# Solar_Batter_Charger_SCH_2.net
KiCad netlist of a schematic drawn in Altium Designer
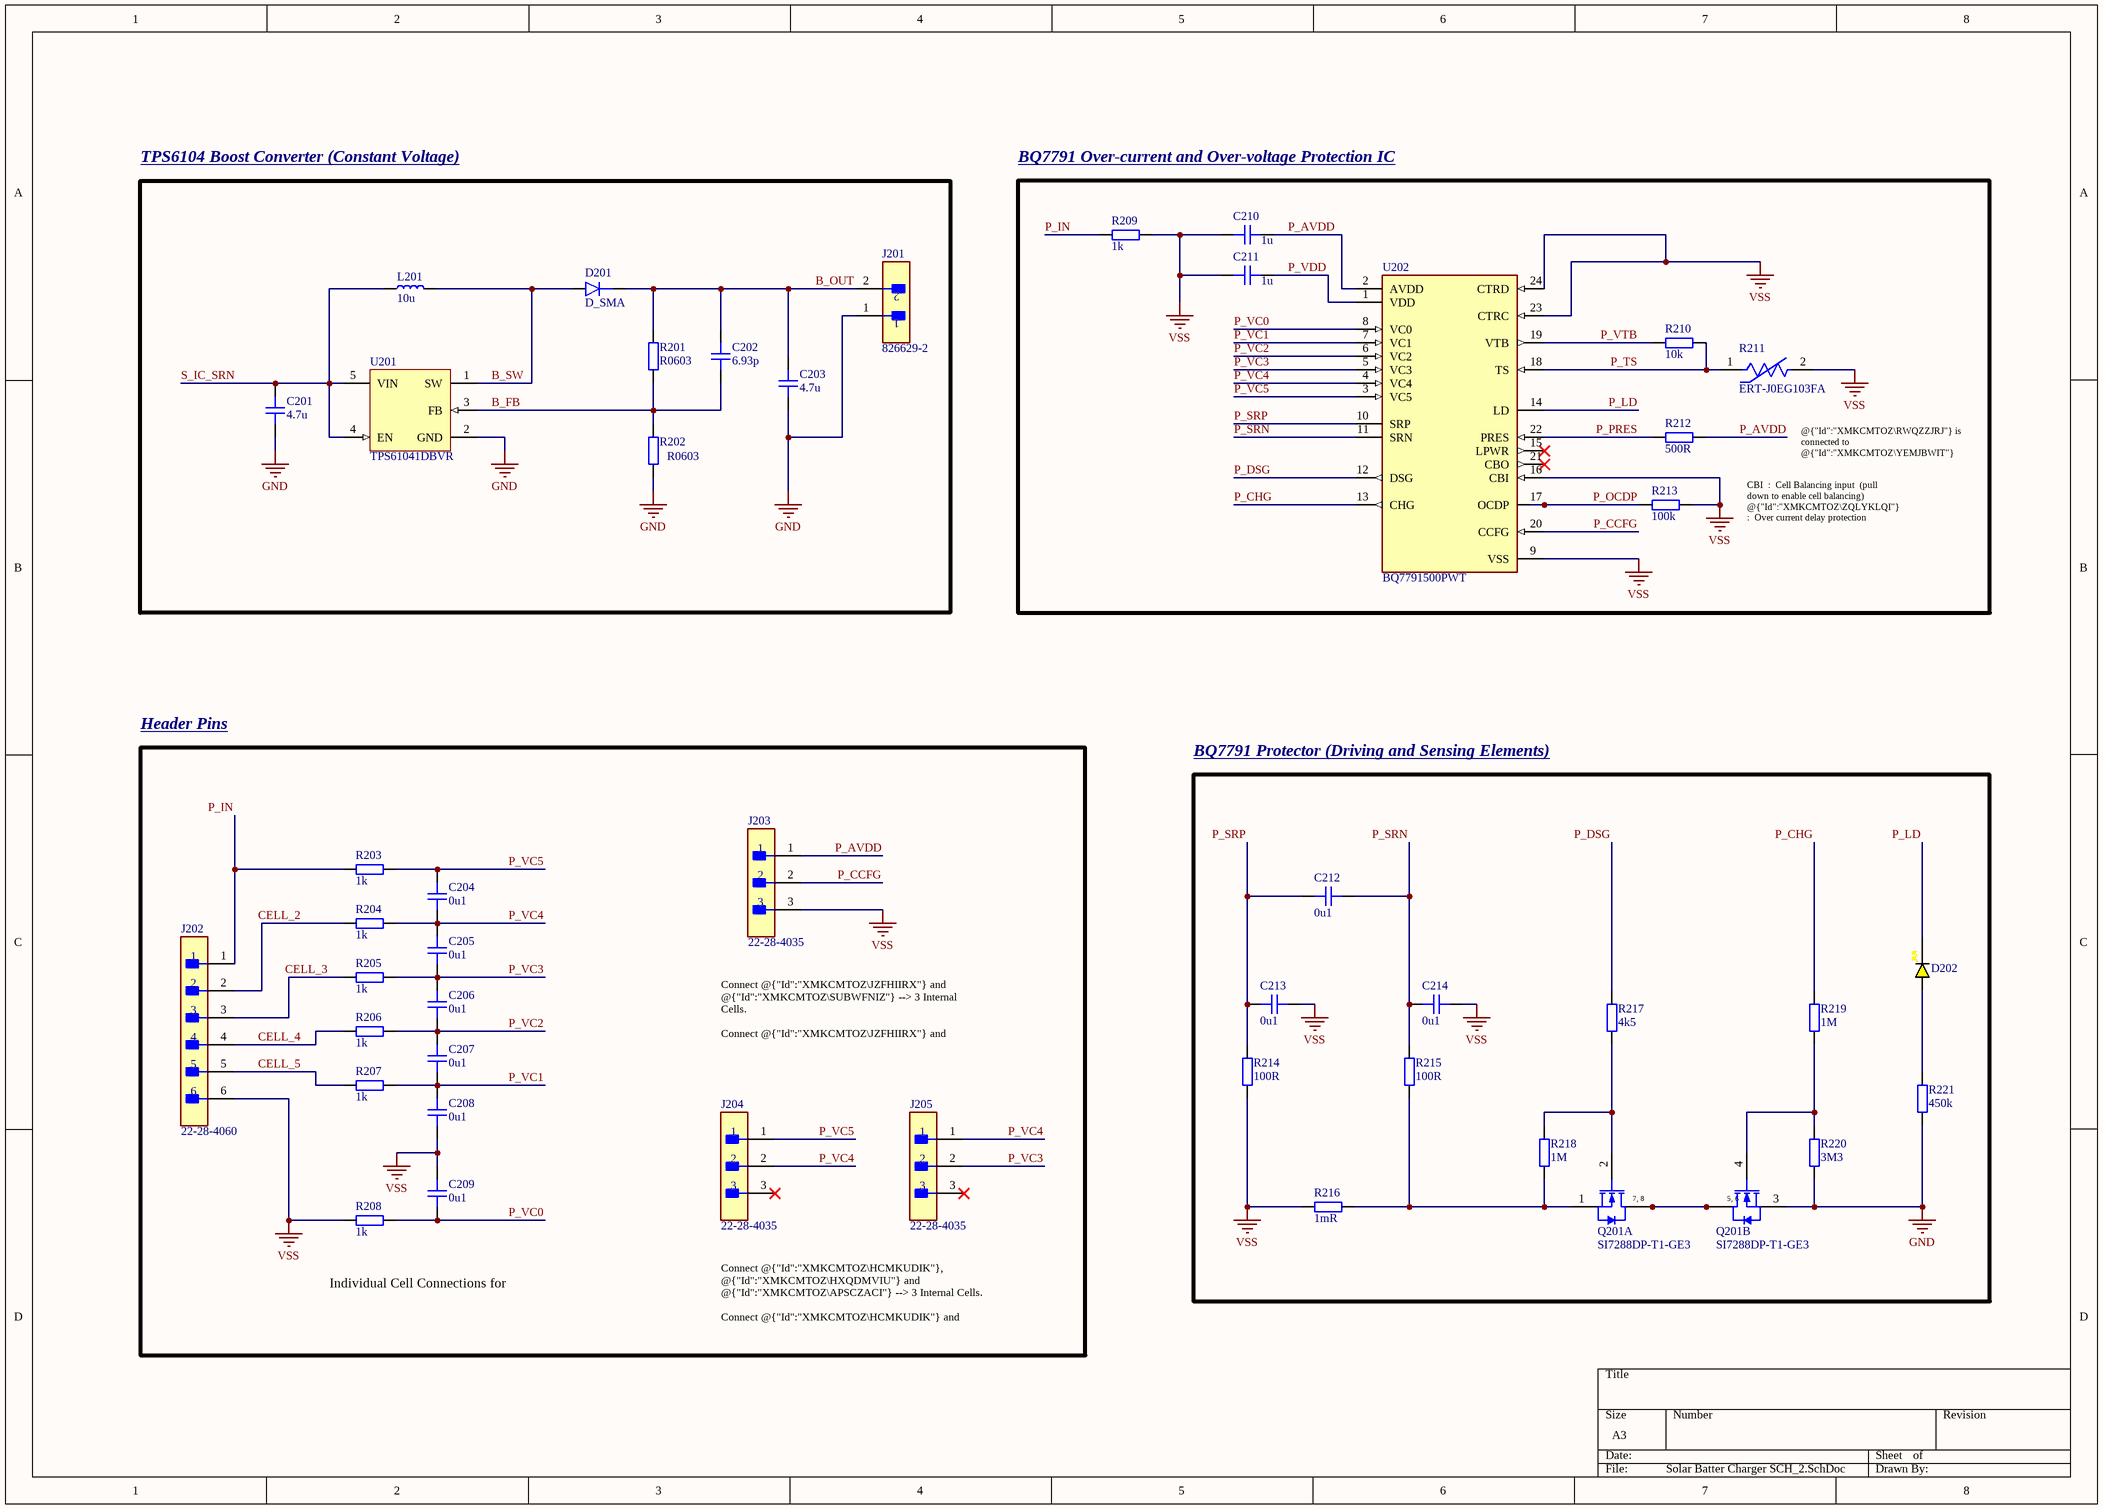
[diagram p0: Solar Batter Charger SCH_2.SchDoc]

(export (version "E")
  (design (tool "Eeschema 10.0.6"))
  (components
    (comp (ref "C201")
      (value "4.7u")
      (footprint "CAP_1210")
      (description "Capacitor SMD 1210")
      (libsource (lib "Schematic-Lib-PhilsLab") (part "CAP_1210"))
    )
    (comp (ref "C202")
      (value "6.93p")
      (footprint "CAP_0805")
      (description "Capacitor SMD 0805")
      (libsource (lib "Schematic-Lib-PhilsLab") (part "CAP_0805"))
    )
    (comp (ref "C203")
      (value "4.7u")
      (footprint "CAP_1210")
      (description "Capacitor SMD 1210")
      (libsource (lib "Schematic-Lib-PhilsLab") (part "CAP_1210"))
    )
    (comp (ref "C204")
      (value "0u1")
      (footprint "CAP_0603")
      (description "Capacitor SMD 0603")
      (libsource (lib "Schematic-Lib-PhilsLab") (part "CAP_0603"))
    )
    (comp (ref "C205")
      (value "0u1")
      (footprint "CAP_0603")
      (description "Capacitor SMD 0603")
      (libsource (lib "Schematic-Lib-PhilsLab") (part "CAP_0603"))
    )
    (comp (ref "C206")
      (value "0u1")
      (footprint "CAP_0603")
      (description "Capacitor SMD 0603")
      (libsource (lib "Schematic-Lib-PhilsLab") (part "CAP_0603"))
    )
    (comp (ref "C207")
      (value "0u1")
      (footprint "CAP_0603")
      (description "Capacitor SMD 0603")
      (libsource (lib "Schematic-Lib-PhilsLab") (part "CAP_0603"))
    )
    (comp (ref "C208")
      (value "0u1")
      (footprint "CAP_0603")
      (description "Capacitor SMD 0603")
      (libsource (lib "Schematic-Lib-PhilsLab") (part "CAP_0603"))
    )
    (comp (ref "C209")
      (value "0u1")
      (footprint "CAP_0603")
      (description "Capacitor SMD 0603")
      (libsource (lib "Schematic-Lib-PhilsLab") (part "CAP_0603"))
    )
    (comp (ref "C210")
      (value "1u")
      (footprint "CAP_0603")
      (description "Capacitor SMD 0603")
      (libsource (lib "Schematic-Lib-PhilsLab") (part "CAP_0603"))
    )
    (comp (ref "C211")
      (value "1u")
      (footprint "CAP_0603")
      (description "Capacitor SMD 0603")
      (libsource (lib "Schematic-Lib-PhilsLab") (part "CAP_0603"))
    )
    (comp (ref "C212")
      (value "0u1")
      (footprint "CAP_0603")
      (description "Capacitor SMD 0603")
      (libsource (lib "Schematic-Lib-PhilsLab") (part "CAP_0603"))
    )
    (comp (ref "C213")
      (value "0u1")
      (footprint "CAP_0603")
      (description "Capacitor SMD 0603")
      (libsource (lib "Schematic-Lib-PhilsLab") (part "CAP_0603"))
    )
    (comp (ref "C214")
      (value "0u1")
      (footprint "CAP_0603")
      (description "Capacitor SMD 0603")
      (libsource (lib "Schematic-Lib-PhilsLab") (part "CAP_0603"))
    )
    (comp (ref "D201")
      (value "D_SMA")
      (footprint "DO-214AC-2 (SMA)")
      (description "Diode SMD SMA (DO-214AA)")
      (libsource (lib "Schematic-Lib-PhilsLab") (part "D_SMA"))
    )
    (comp (ref "D202")
      (value "YELLOW")
      (footprint "LED_0603_YELLOW")
      (description "LED 0603 YELLOW SMD")
      (libsource (lib "Schematic-Lib-PhilsLab") (part "LED_0603_YELLOW"))
    )
    (comp (ref "J201")
      (value "826629-2")
      (footprint "FP-826629-2-MFG")
      (description "CONN HEADER VERT 2POS 2.54MM")
      (libsource (lib "Altium Content Vault") (part "3bc925449376181038e59eaffc5286c"))
    )
    (comp (ref "J202")
      (value "22-28-4060")
      (footprint "FP-22-28-4060-MFG")
      (description "CONN HEADER VERT 6POS 2.54MM")
      (libsource (lib "Altium Content Vault") (part "f2cb566baf1c37ab5a3b8e90bbeafd6"))
    )
    (comp (ref "J203")
      (value "22-28-4035")
      (footprint "FP-22-28-4035-MFG")
      (libsource (lib "Altium Content Vault") (part "0d3f023dd272f625e17a2be33dea85f"))
    )
    (comp (ref "J204")
      (value "22-28-4035")
      (footprint "FP-22-28-4035-MFG")
      (libsource (lib "Altium Content Vault") (part "0d3f023dd272f625e17a2be33dea85f"))
    )
    (comp (ref "J205")
      (value "22-28-4035")
      (footprint "FP-22-28-4035-MFG")
      (libsource (lib "Altium Content Vault") (part "0d3f023dd272f625e17a2be33dea85f"))
    )
    (comp (ref "L201")
      (value "10u")
      (footprint "NRS5020")
      (description "NRS5020 SMD Power Inductor Taiyo Yuden")
      (fields (field (name "MANUFACTURER") "Taiyo Yuden") (field (name "MANUFACTURER PART NUMBER") "NRS5020"))
      (libsource (lib "Schematic-Lib-PhilsLab") (part "NRS5020"))
    )
    (comp (ref "Q201")
      (value "SI7288DP-T1-GE3")
      (footprint "VISH-POWERPAKSO-8_A_V")
      (description "Dual N-Channel (D-S) MOSFET, 40 V, 20 A, -55 to 150 degC, 8-Pin POWERPAKSO-8, RoHS, Tape and Reel")
      (fields (field (name "MANUFACTURER") "Vishay"))
      (libsource (lib "Altium Content Vault") (part "NEMOS-SGDD-SGDD-8"))
    )
    (comp (ref "R201")
      (value "R0603")
      (footprint "RES_0603")
      (description "Resistor SMD 0603")
      (libsource (lib "Schematic-Lib-PhilsLab") (part "RES_0603"))
    )
    (comp (ref "R202")
      (value "R0603")
      (footprint "RES_0603")
      (description "Resistor SMD 0603")
      (libsource (lib "Schematic-Lib-PhilsLab") (part "RES_0603"))
    )
    (comp (ref "R203")
      (value "1k")
      (footprint "RES_0603")
      (description "Resistor SMD 0603")
      (libsource (lib "Schematic-Lib-PhilsLab") (part "RES_0603"))
    )
    (comp (ref "R204")
      (value "1k")
      (footprint "RES_0603")
      (description "Resistor SMD 0603")
      (libsource (lib "Schematic-Lib-PhilsLab") (part "RES_0603"))
    )
    (comp (ref "R205")
      (value "1k")
      (footprint "RES_0603")
      (description "Resistor SMD 0603")
      (libsource (lib "Schematic-Lib-PhilsLab") (part "RES_0603"))
    )
    (comp (ref "R206")
      (value "1k")
      (footprint "RES_0603")
      (description "Resistor SMD 0603")
      (libsource (lib "Schematic-Lib-PhilsLab") (part "RES_0603"))
    )
    (comp (ref "R207")
      (value "1k")
      (footprint "RES_0603")
      (description "Resistor SMD 0603")
      (libsource (lib "Schematic-Lib-PhilsLab") (part "RES_0603"))
    )
    (comp (ref "R208")
      (value "1k")
      (footprint "RES_0603")
      (description "Resistor SMD 0603")
      (libsource (lib "Schematic-Lib-PhilsLab") (part "RES_0603"))
    )
    (comp (ref "R209")
      (value "1k")
      (footprint "RES_0603")
      (description "Resistor SMD 0603")
      (libsource (lib "Schematic-Lib-PhilsLab") (part "RES_0603"))
    )
    (comp (ref "R210")
      (value "10k")
      (footprint "RES_0402")
      (description "Resistor SMD 0402")
      (libsource (lib "Schematic-Lib-PhilsLab") (part "RES_0402"))
    )
    (comp (ref "R211")
      (value "ERT-J0EG103FA")
      (footprint "FP-ERTJ0-MFG")
      (description "THERMISTOR NTC 10KOHM 3380K 0402")
      (fields (field (name "TOLERANCE") "1%"))
      (libsource (lib "Altium Content Vault") (part "3b148a6ebabc5fb4d708a66c052d352"))
    )
    (comp (ref "R212")
      (value "500R")
      (footprint "RES_0402")
      (description "Resistor SMD 0402")
      (libsource (lib "Schematic-Lib-PhilsLab") (part "RES_0402"))
    )
    (comp (ref "R213")
      (value "100k")
      (footprint "RES_0805")
      (description "Resistor SMD 0805")
      (libsource (lib "Schematic-Lib-PhilsLab") (part "RES_0805"))
    )
    (comp (ref "R214")
      (value "100R")
      (footprint "RES_0402")
      (description "Resistor SMD 0402")
      (libsource (lib "Schematic-Lib-PhilsLab") (part "RES_0402"))
    )
    (comp (ref "R215")
      (value "100R")
      (footprint "RES_0402")
      (description "Resistor SMD 0402")
      (libsource (lib "Schematic-Lib-PhilsLab") (part "RES_0402"))
    )
    (comp (ref "R216")
      (value "1mR")
      (footprint "RES_0603")
      (description "Resistor SMD 0603")
      (libsource (lib "Schematic-Lib-PhilsLab") (part "RES_0603"))
    )
    (comp (ref "R217")
      (value "4k5")
      (footprint "RES_0805")
      (description "Resistor SMD 0805")
      (libsource (lib "Schematic-Lib-PhilsLab") (part "RES_0805"))
    )
    (comp (ref "R218")
      (value "1M")
      (footprint "RES_0805")
      (description "Resistor SMD 0805")
      (libsource (lib "Schematic-Lib-PhilsLab") (part "RES_0805"))
    )
    (comp (ref "R219")
      (value "1M")
      (footprint "RES_0805")
      (description "Resistor SMD 0805")
      (libsource (lib "Schematic-Lib-PhilsLab") (part "RES_0805"))
    )
    (comp (ref "R220")
      (value "3M3")
      (footprint "RES_0805")
      (description "Resistor SMD 0805")
      (libsource (lib "Schematic-Lib-PhilsLab") (part "RES_0805"))
    )
    (comp (ref "R221")
      (value "450k")
      (footprint "RES_0805")
      (description "Resistor SMD 0805")
      (libsource (lib "Schematic-Lib-PhilsLab") (part "RES_0805"))
    )
    (comp (ref "U201")
      (value "TPS61041DBVR")
      (footprint "DBV0005A_M")
      (fields (field (name "MANUFACTURER") "Texas Instruments"))
      (libsource (lib "Altium Content Vault") (part "TI-TPS61041DBV5"))
    )
    (comp (ref "U202")
      (value "BQ7791500PWT")
      (footprint "FP-PW0024A-MFG")
      (description "3-SERIES TO 5-SERIES STACKABLE U")
      (fields
        (field (name "OCTOPART") "https://octopart.com/bq7791500pwt-texas+instruments-90752675")
        (field (name "MANUFACTURER") "Texas Instruments")
      )
      (libsource (lib "Altium Content Vault") (part "3b3e6f42bdc68e1b6fa831f7f6c6a1b"))
    )
  )
  (nets
    (net (code "1") (name "/B_FB") (class "Default")
      (node (ref "C202") (pin "2") (pinfunction "2_2") (pintype "passive"))
      (node (ref "R201") (pin "1") (pinfunction "1_1") (pintype "passive"))
      (node (ref "R202") (pin "2") (pinfunction "2_2") (pintype "passive"))
      (node (ref "U201") (pin "3") (pinfunction "FB_3") (pintype "input"))
    )
    (net (code "2") (name "/B_OUT") (class "Default")
      (node (ref "C202") (pin "1") (pinfunction "1_1") (pintype "passive"))
      (node (ref "C203") (pin "2") (pinfunction "2_2") (pintype "passive"))
      (node (ref "D201") (pin "K") (pinfunction "K_K") (pintype "passive"))
      (node (ref "J201") (pin "2") (pinfunction "2_2") (pintype "passive"))
      (node (ref "R201") (pin "2") (pinfunction "2_2") (pintype "passive"))
    )
    (net (code "3") (name "/B_SW") (class "Default")
      (node (ref "D201") (pin "A") (pinfunction "A_A") (pintype "passive"))
      (node (ref "L201") (pin "2") (pinfunction "2_2") (pintype "passive"))
      (node (ref "U201") (pin "1") (pinfunction "SW_1") (pintype "power_in"))
    )
    (net (code "4") (name "/CELL_2") (class "Default")
      (node (ref "J202") (pin "2") (pinfunction "2_2") (pintype "passive"))
      (node (ref "R204") (pin "1") (pinfunction "1_1") (pintype "passive"))
    )
    (net (code "5") (name "/CELL_3") (class "Default")
      (node (ref "J202") (pin "3") (pinfunction "3_3") (pintype "passive"))
      (node (ref "R205") (pin "1") (pinfunction "1_1") (pintype "passive"))
    )
    (net (code "6") (name "/CELL_4") (class "Default")
      (node (ref "J202") (pin "4") (pinfunction "4_4") (pintype "passive"))
      (node (ref "R206") (pin "1") (pinfunction "1_1") (pintype "passive"))
    )
    (net (code "7") (name "/CELL_5") (class "Default")
      (node (ref "J202") (pin "5") (pinfunction "5_5") (pintype "passive"))
      (node (ref "R207") (pin "1") (pinfunction "1_1") (pintype "passive"))
    )
    (net (code "8") (name "/P_AVDD") (class "Default")
      (node (ref "C210") (pin "2") (pinfunction "2_2") (pintype "passive"))
      (node (ref "J203") (pin "1") (pinfunction "1_1") (pintype "passive"))
      (node (ref "R212") (pin "2") (pinfunction "2_2") (pintype "passive"))
      (node (ref "U202") (pin "2") (pinfunction "AVDD_2") (pintype "power_in"))
    )
    (net (code "9") (name "/P_CCFG") (class "Default")
      (node (ref "J203") (pin "2") (pinfunction "2_2") (pintype "passive"))
      (node (ref "U202") (pin "20") (pinfunction "CCFG_20") (pintype "input"))
    )
    (net (code "10") (name "/P_CHG") (class "Default")
      (node (ref "R219") (pin "2") (pinfunction "2_2") (pintype "passive"))
      (node (ref "U202") (pin "13") (pinfunction "CHG_13") (pintype "output"))
    )
    (net (code "11") (name "/P_DSG") (class "Default")
      (node (ref "R217") (pin "2") (pinfunction "2_2") (pintype "passive"))
      (node (ref "U202") (pin "12") (pinfunction "DSG_12") (pintype "output"))
    )
    (net (code "12") (name "/P_IN") (class "Default")
      (node (ref "J202") (pin "1") (pinfunction "1_1") (pintype "passive"))
      (node (ref "R203") (pin "1") (pinfunction "1_1") (pintype "passive"))
      (node (ref "R209") (pin "1") (pinfunction "1_1") (pintype "passive"))
    )
    (net (code "13") (name "/P_LD") (class "Default")
      (node (ref "D202") (pin "K") (pinfunction "K_K") (pintype "passive"))
      (node (ref "U202") (pin "14") (pinfunction "LD_14") (pintype "passive"))
    )
    (net (code "14") (name "/P_OCDP") (class "Default")
      (node (ref "R213") (pin "1") (pinfunction "1_1") (pintype "passive"))
      (node (ref "U202") (pin "17") (pinfunction "OCDP_17") (pintype "passive"))
    )
    (net (code "15") (name "/P_PRES") (class "Default")
      (node (ref "R212") (pin "1") (pinfunction "1_1") (pintype "passive"))
      (node (ref "U202") (pin "22") (pinfunction "PRES_22") (pintype "input"))
    )
    (net (code "16") (name "/P_SRN") (class "Default")
      (node (ref "C212") (pin "2") (pinfunction "2_2") (pintype "passive"))
      (node (ref "C214") (pin "1") (pinfunction "1_1") (pintype "passive"))
      (node (ref "R215") (pin "2") (pinfunction "2_2") (pintype "passive"))
      (node (ref "U202") (pin "11") (pinfunction "SRN_11") (pintype "passive"))
    )
    (net (code "17") (name "/P_SRP") (class "Default")
      (node (ref "C212") (pin "1") (pinfunction "1_1") (pintype "passive"))
      (node (ref "C213") (pin "1") (pinfunction "1_1") (pintype "passive"))
      (node (ref "R214") (pin "2") (pinfunction "2_2") (pintype "passive"))
      (node (ref "U202") (pin "10") (pinfunction "SRP_10") (pintype "passive"))
    )
    (net (code "18") (name "/P_TS") (class "Default")
      (node (ref "R210") (pin "2") (pinfunction "2_2") (pintype "passive"))
      (node (ref "R211") (pin "1") (pinfunction "1_1") (pintype "passive"))
      (node (ref "U202") (pin "18") (pinfunction "TS_18") (pintype "input"))
    )
    (net (code "19") (name "/P_VC0") (class "Default")
      (node (ref "C209") (pin "2") (pinfunction "2_2") (pintype "passive"))
      (node (ref "R208") (pin "2") (pinfunction "2_2") (pintype "passive"))
      (node (ref "U202") (pin "8") (pinfunction "VC0_8") (pintype "input"))
    )
    (net (code "20") (name "/P_VC1") (class "Default")
      (node (ref "C207") (pin "2") (pinfunction "2_2") (pintype "passive"))
      (node (ref "C208") (pin "1") (pinfunction "1_1") (pintype "passive"))
      (node (ref "R207") (pin "2") (pinfunction "2_2") (pintype "passive"))
      (node (ref "U202") (pin "7") (pinfunction "VC1_7") (pintype "input"))
    )
    (net (code "21") (name "/P_VC2") (class "Default")
      (node (ref "C206") (pin "2") (pinfunction "2_2") (pintype "passive"))
      (node (ref "C207") (pin "1") (pinfunction "1_1") (pintype "passive"))
      (node (ref "R206") (pin "2") (pinfunction "2_2") (pintype "passive"))
      (node (ref "U202") (pin "6") (pinfunction "VC2_6") (pintype "input"))
    )
    (net (code "22") (name "/P_VC3") (class "Default")
      (node (ref "C205") (pin "2") (pinfunction "2_2") (pintype "passive"))
      (node (ref "C206") (pin "1") (pinfunction "1_1") (pintype "passive"))
      (node (ref "J205") (pin "2") (pinfunction "2_2") (pintype "passive"))
      (node (ref "R205") (pin "2") (pinfunction "2_2") (pintype "passive"))
      (node (ref "U202") (pin "5") (pinfunction "VC3_5") (pintype "input"))
    )
    (net (code "23") (name "/P_VC4") (class "Default")
      (node (ref "C204") (pin "2") (pinfunction "2_2") (pintype "passive"))
      (node (ref "C205") (pin "1") (pinfunction "1_1") (pintype "passive"))
      (node (ref "J204") (pin "2") (pinfunction "2_2") (pintype "passive"))
      (node (ref "J205") (pin "1") (pinfunction "1_1") (pintype "passive"))
      (node (ref "R204") (pin "2") (pinfunction "2_2") (pintype "passive"))
      (node (ref "U202") (pin "4") (pinfunction "VC4_4") (pintype "input"))
    )
    (net (code "24") (name "/P_VC5") (class "Default")
      (node (ref "C204") (pin "1") (pinfunction "1_1") (pintype "passive"))
      (node (ref "J204") (pin "1") (pinfunction "1_1") (pintype "passive"))
      (node (ref "R203") (pin "2") (pinfunction "2_2") (pintype "passive"))
      (node (ref "U202") (pin "3") (pinfunction "VC5_3") (pintype "input"))
    )
    (net (code "25") (name "/P_VDD") (class "Default")
      (node (ref "C211") (pin "2") (pinfunction "2_2") (pintype "passive"))
      (node (ref "U202") (pin "1") (pinfunction "VDD_1") (pintype "power_in"))
    )
    (net (code "26") (name "/P_VTB") (class "Default")
      (node (ref "R210") (pin "1") (pinfunction "1_1") (pintype "passive"))
      (node (ref "U202") (pin "19") (pinfunction "VTB_19") (pintype "output"))
    )
    (net (code "27") (name "/S_IC_SRN") (class "Default")
      (node (ref "C201") (pin "2") (pinfunction "2_2") (pintype "passive"))
      (node (ref "L201") (pin "1") (pinfunction "1_1") (pintype "passive"))
      (node (ref "U201") (pin "4") (pinfunction "EN_4") (pintype "input"))
      (node (ref "U201") (pin "5") (pinfunction "VIN_5") (pintype "power_in"))
    )
    (net (code "28") (name "GND") (class "Default")
      (node (ref "C201") (pin "1") (pinfunction "1_1") (pintype "passive"))
      (node (ref "C203") (pin "1") (pinfunction "1_1") (pintype "passive"))
      (node (ref "J201") (pin "1") (pinfunction "1_1") (pintype "passive"))
      (node (ref "Q201") (pin "3") (pinfunction "S2_3") (pintype "passive"))
      (node (ref "R202") (pin "1") (pinfunction "1_1") (pintype "passive"))
      (node (ref "R220") (pin "1") (pinfunction "1_1") (pintype "passive"))
      (node (ref "R221") (pin "1") (pinfunction "1_1") (pintype "passive"))
      (node (ref "U201") (pin "2") (pinfunction "GND_2") (pintype "power_in"))
    )
    (net (code "29") (name "Net-(D202-PadA)") (class "Default")
      (node (ref "D202") (pin "A") (pinfunction "A_A") (pintype "passive"))
      (node (ref "R221") (pin "2") (pinfunction "2_2") (pintype "passive"))
    )
    (net (code "30") (name "Net-(Q201A-D1-Pad7)") (class "Default")
      (node (ref "Q201") (pin "5") (pinfunction "D2_5") (pintype "passive"))
      (node (ref "Q201") (pin "6") (pinfunction "D2_6") (pintype "passive"))
      (node (ref "Q201") (pin "7") (pinfunction "D1_7") (pintype "passive"))
      (node (ref "Q201") (pin "8") (pinfunction "D1_8") (pintype "passive"))
    )
    (net (code "31") (name "Net-(Q201A-G1)") (class "Default")
      (node (ref "Q201") (pin "2") (pinfunction "G1_2") (pintype "passive"))
      (node (ref "R217") (pin "1") (pinfunction "1_1") (pintype "passive"))
      (node (ref "R218") (pin "2") (pinfunction "2_2") (pintype "passive"))
    )
    (net (code "32") (name "Net-(Q201A-S1)") (class "Default")
      (node (ref "Q201") (pin "1") (pinfunction "S1_1") (pintype "passive"))
      (node (ref "R215") (pin "1") (pinfunction "1_1") (pintype "passive"))
      (node (ref "R216") (pin "1") (pinfunction "1_1") (pintype "passive"))
      (node (ref "R218") (pin "1") (pinfunction "1_1") (pintype "passive"))
    )
    (net (code "33") (name "Net-(Q201B-G2)") (class "Default")
      (node (ref "Q201") (pin "4") (pinfunction "G2_4") (pintype "passive"))
      (node (ref "R219") (pin "1") (pinfunction "1_1") (pintype "passive"))
      (node (ref "R220") (pin "2") (pinfunction "2_2") (pintype "passive"))
    )
    (net (code "34") (name "VSS") (class "Default")
      (node (ref "C208") (pin "2") (pinfunction "2_2") (pintype "passive"))
      (node (ref "C209") (pin "1") (pinfunction "1_1") (pintype "passive"))
      (node (ref "C210") (pin "1") (pinfunction "1_1") (pintype "passive"))
      (node (ref "C211") (pin "1") (pinfunction "1_1") (pintype "passive"))
      (node (ref "C213") (pin "2") (pinfunction "2_2") (pintype "passive"))
      (node (ref "C214") (pin "2") (pinfunction "2_2") (pintype "passive"))
      (node (ref "J202") (pin "6") (pinfunction "6_6") (pintype "passive"))
      (node (ref "J203") (pin "3") (pinfunction "3_3") (pintype "passive"))
      (node (ref "R208") (pin "1") (pinfunction "1_1") (pintype "passive"))
      (node (ref "R209") (pin "2") (pinfunction "2_2") (pintype "passive"))
      (node (ref "R211") (pin "2") (pinfunction "2_2") (pintype "passive"))
      (node (ref "R213") (pin "2") (pinfunction "2_2") (pintype "passive"))
      (node (ref "R214") (pin "1") (pinfunction "1_1") (pintype "passive"))
      (node (ref "R216") (pin "2") (pinfunction "2_2") (pintype "passive"))
      (node (ref "U202") (pin "16") (pinfunction "CBI_16") (pintype "input"))
      (node (ref "U202") (pin "23") (pinfunction "CTRC_23") (pintype "input"))
      (node (ref "U202") (pin "24") (pinfunction "CTRD_24") (pintype "input"))
      (node (ref "U202") (pin "9") (pinfunction "VSS_9") (pintype "power_in"))
    )
    (net (code "35") (name "unconnected-(J204-Pad3)") (class "Default")
      (node (ref "J204") (pin "3") (pinfunction "3_3") (pintype "passive+no_connect"))
    )
    (net (code "36") (name "unconnected-(J205-Pad3)") (class "Default")
      (node (ref "J205") (pin "3") (pinfunction "3_3") (pintype "passive+no_connect"))
    )
    (net (code "37") (name "unconnected-(U202-CBO-Pad21)") (class "Default")
      (node (ref "U202") (pin "21") (pinfunction "CBO_21") (pintype "output+no_connect"))
    )
    (net (code "38") (name "unconnected-(U202-LPWR-Pad15)") (class "Default")
      (node (ref "U202") (pin "15") (pinfunction "LPWR_15") (pintype "output+no_connect"))
    )
  )
)
